# ProPrj___2025-12-14-16-21-23.net
KiCad netlist of a schematic drawn in EasyEDA Pro
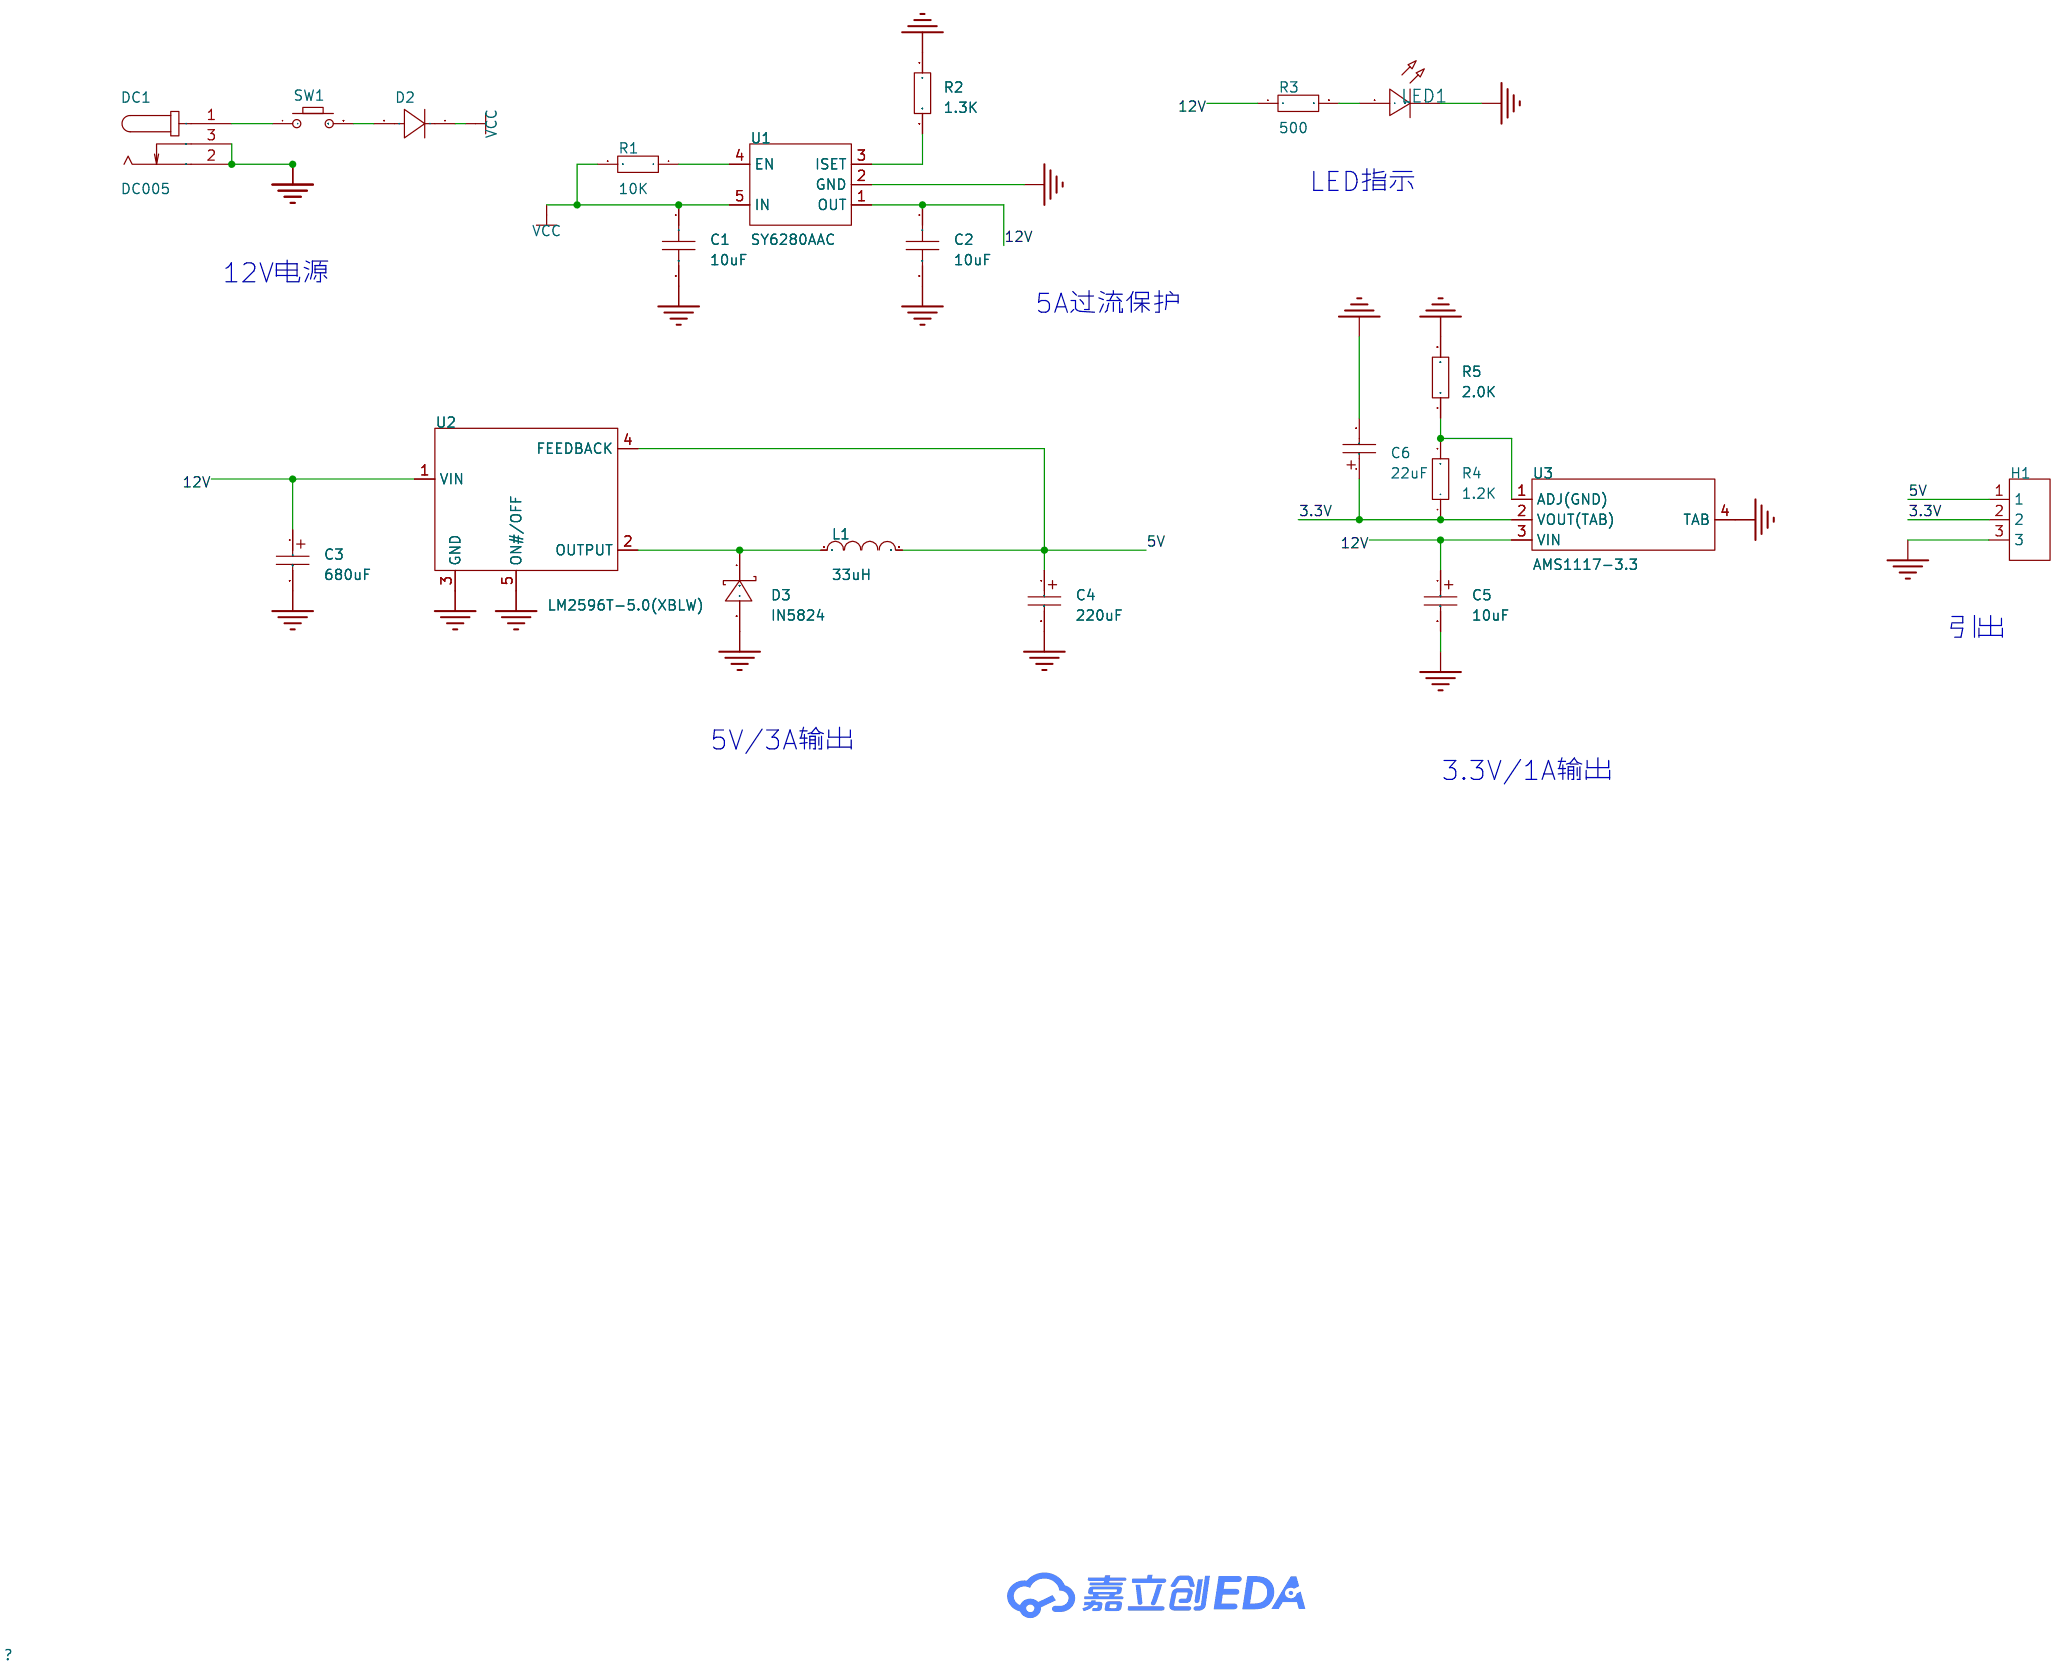
[diagram p0: schematic sheet]

(export (version "E")
  (design (tool "Eeschema 10.0.6"))
  (components
    (comp (ref "C1")
      (value "10uF")
      (footprint "easyedapro:C0603")
      (libsource (lib "easyedapro") (part "Capacitance"))
    )
    (comp (ref "C2")
      (value "10uF")
      (footprint "easyedapro:C0603")
      (libsource (lib "easyedapro") (part "Capacitance"))
    )
    (comp (ref "C3")
      (value "680uF")
      (footprint "easyedapro:C_Ele_SMD_3x5.4mm")
      (libsource (lib "easyedapro") (part "CAP"))
    )
    (comp (ref "C4")
      (value "220uF")
      (footprint "easyedapro:C_Ele_SMD_3x5.4mm")
      (libsource (lib "easyedapro") (part "CAP"))
    )
    (comp (ref "C5")
      (value "10uF")
      (footprint "easyedapro:C_Ele_SMD_3x5.4mm")
      (libsource (lib "easyedapro") (part "CAP"))
    )
    (comp (ref "C6")
      (value "22uF")
      (footprint "easyedapro:C_Ele_SMD_3x5.4mm")
      (libsource (lib "easyedapro") (part "CAP"))
    )
    (comp (ref "D2")
      (value "~")
      (footprint "easyedapro:DO_1N4007")
      (libsource (lib "easyedapro") (part "D_1N4007"))
    )
    (comp (ref "D3")
      (value "IN5824")
      (footprint "easyedapro:SMAF_L3.5-W2.6-LS4.7-RD")
      (libsource (lib "easyedapro") (part "IN5824"))
    )
    (comp (ref "DC1")
      (value "DC005")
      (footprint "easyedapro:DC-IN-TH_DC005")
      (description "连接器类型:DC电源插座;安装方式:弯插;触点内径:2mm;触点外径:6.3mm;额定电流:500mA;额定电压:12V;工作温度:-30°C~+70°C;")
      (fields (field (name "Manufacturer") "SHOU HAN(首韩)"))
      (libsource (lib "easyedapro") (part "DC005_C431533"))
    )
    (comp (ref "H1")
      (value "~")
      (footprint "easyedapro:HDR-TH_3P-P2.54-V-F")
      (libsource (lib "easyedapro") (part "PM254V-11-03-H85"))
    )
    (comp (ref "L1")
      (value "33uH")
      (footprint "easyedapro:L0603")
      (libsource (lib "easyedapro") (part "SDFL1608S100KTF"))
    )
    (comp (ref "LED1")
      (value "~")
      (footprint "easyedapro:LED_0603")
      (libsource (lib "easyedapro") (part "LED_R"))
    )
    (comp (ref "R1") (value "10K") (footprint "easyedapro:R0603") (libsource (lib "easyedapro") (part "电阻")))
    (comp (ref "R2") (value "1.3K") (footprint "easyedapro:R0603") (libsource (lib "easyedapro") (part "电阻")))
    (comp (ref "R3") (value "500") (footprint "easyedapro:R0603") (libsource (lib "easyedapro") (part "电阻")))
    (comp (ref "R4") (value "1.2K") (footprint "easyedapro:R0603") (libsource (lib "easyedapro") (part "电阻")))
    (comp (ref "R5") (value "2.0K") (footprint "easyedapro:R0603") (libsource (lib "easyedapro") (part "电阻")))
    (comp (ref "SW1")
      (value "~")
      (footprint "easyedapro:Key_TH_3.5x6x4.3")
      (libsource (lib "easyedapro") (part "Key_TH_3.5x6x4.3"))
    )
    (comp (ref "U1")
      (value "SY6280AAC")
      (footprint "easyedapro:SOT-23-5_L3.0-W1.7-P0.95-LS2.8-BR")
      (libsource (lib "easyedapro") (part "SY6280AAC_C9900003867"))
    )
    (comp (ref "U2")
      (value "LM2596T-5.0(XBLW)")
      (footprint "easyedapro:TO-220-5L_L10.2-W4.5-P1.71-L")
      (description "功能类型:降压型;工作电压:6V~40V;输出电压:5V;输出电流:3A;输出类型:固定;")
      (fields (field (name "Manufacturer") "XBLW(芯伯乐)"))
      (libsource (lib "easyedapro") (part "LM2596T-5.0(XBLW)"))
    )
    (comp (ref "U3")
      (value "AMS1117-3.3")
      (footprint "easyedapro:SOT-223-4_L6.5-W3.5-P2.30-LS7.0-BR")
      (description "输出类型:固定;工作电压:12V;输出电压:3.3V;输出电流:1A;电源纹波抑制比(PSRR):60dB@(120Hz);输出极性:正极;")
      (fields (field (name "Manufacturer") "UMW(友台半导体)"))
      (libsource (lib "easyedapro") (part "AMS1117-3.3_C347222"))
    )
  )
  (nets
    (net (code "1") (name "/3.3V") (class "Default")
      (node (ref "C6") (pin "1") (pinfunction "1_1") (pintype "input"))
      (node (ref "H1") (pin "2") (pinfunction "2_2") (pintype "unspecified"))
      (node (ref "R4") (pin "1") (pinfunction "1_1") (pintype "input"))
      (node (ref "U3") (pin "2") (pinfunction "VOUT(TAB)_2") (pintype "unspecified"))
    )
    (net (code "2") (name "/5V") (class "Default")
      (node (ref "C4") (pin "1") (pinfunction "1_1") (pintype "input"))
      (node (ref "H1") (pin "1") (pinfunction "1_1") (pintype "unspecified"))
      (node (ref "L1") (pin "2") (pinfunction "2_2") (pintype "unspecified"))
      (node (ref "U2") (pin "4") (pinfunction "FEEDBACK_4") (pintype "unspecified"))
    )
    (net (code "3") (name "/12V") (class "Default")
      (node (ref "C2") (pin "1") (pinfunction "1_1") (pintype "input"))
      (node (ref "C3") (pin "1") (pinfunction "1_1") (pintype "input"))
      (node (ref "C5") (pin "1") (pinfunction "1_1") (pintype "input"))
      (node (ref "R3") (pin "1") (pinfunction "1_1") (pintype "input"))
      (node (ref "U1") (pin "1") (pinfunction "OUT_1") (pintype "unspecified"))
      (node (ref "U2") (pin "1") (pinfunction "VIN_1") (pintype "unspecified"))
      (node (ref "U3") (pin "3") (pinfunction "VIN_3") (pintype "unspecified"))
    )
    (net (code "4") (name "GND") (class "Default")
      (node (ref "C1") (pin "2") (pinfunction "2_2") (pintype "input"))
      (node (ref "C2") (pin "2") (pinfunction "2_2") (pintype "input"))
      (node (ref "C3") (pin "2") (pinfunction "2_2") (pintype "input"))
      (node (ref "C4") (pin "2") (pinfunction "2_2") (pintype "input"))
      (node (ref "C5") (pin "2") (pinfunction "2_2") (pintype "input"))
      (node (ref "C6") (pin "2") (pinfunction "2_2") (pintype "input"))
      (node (ref "D3") (pin "2") (pinfunction "A_2") (pintype "unspecified"))
      (node (ref "DC1") (pin "2") (pinfunction "2_2") (pintype "unspecified"))
      (node (ref "DC1") (pin "3") (pinfunction "3_3") (pintype "unspecified"))
      (node (ref "H1") (pin "3") (pinfunction "3_3") (pintype "unspecified"))
      (node (ref "LED1") (pin "1") (pinfunction "C_1") (pintype "input"))
      (node (ref "R2") (pin "1") (pinfunction "1_1") (pintype "input"))
      (node (ref "R5") (pin "2") (pinfunction "2_2") (pintype "input"))
      (node (ref "U1") (pin "2") (pinfunction "GND_2") (pintype "unspecified"))
      (node (ref "U2") (pin "3") (pinfunction "GND_3") (pintype "unspecified"))
      (node (ref "U2") (pin "5") (pinfunction "ON#/OFF_5") (pintype "unspecified"))
      (node (ref "U3") (pin "4") (pinfunction "TAB_4") (pintype "unspecified"))
    )
    (net (code "5") (name "Net-(D2-A)") (class "Default")
      (node (ref "D2") (pin "2") (pinfunction "A_2") (pintype "input"))
      (node (ref "SW1") (pin "B") (pinfunction "B_B") (pintype "input"))
    )
    (net (code "6") (name "Net-(D3-C)") (class "Default")
      (node (ref "D3") (pin "1") (pinfunction "C_1") (pintype "unspecified"))
      (node (ref "L1") (pin "1") (pinfunction "1_1") (pintype "unspecified"))
      (node (ref "U2") (pin "2") (pinfunction "OUTPUT_2") (pintype "unspecified"))
    )
    (net (code "7") (name "Net-(DC1-Pad1)") (class "Default")
      (node (ref "DC1") (pin "1") (pinfunction "1_1") (pintype "unspecified"))
      (node (ref "SW1") (pin "A") (pinfunction "A_A") (pintype "input"))
    )
    (net (code "8") (name "Net-(LED1-A)") (class "Default")
      (node (ref "LED1") (pin "2") (pinfunction "A_2") (pintype "input"))
      (node (ref "R3") (pin "2") (pinfunction "2_2") (pintype "input"))
    )
    (net (code "9") (name "Net-(U1-EN)") (class "Default")
      (node (ref "R1") (pin "1") (pinfunction "1_1") (pintype "input"))
      (node (ref "U1") (pin "4") (pinfunction "EN_4") (pintype "unspecified"))
    )
    (net (code "10") (name "Net-(U1-ISET)") (class "Default")
      (node (ref "R2") (pin "2") (pinfunction "2_2") (pintype "input"))
      (node (ref "U1") (pin "3") (pinfunction "ISET_3") (pintype "unspecified"))
    )
    (net (code "11") (name "Net-(U3-ADJ(GND))") (class "Default")
      (node (ref "R4") (pin "2") (pinfunction "2_2") (pintype "input"))
      (node (ref "R5") (pin "1") (pinfunction "1_1") (pintype "input"))
      (node (ref "U3") (pin "1") (pinfunction "ADJ(GND)_1") (pintype "unspecified"))
    )
    (net (code "12") (name "VCC") (class "Default")
      (node (ref "C1") (pin "1") (pinfunction "1_1") (pintype "input"))
      (node (ref "D2") (pin "1") (pinfunction "K_1") (pintype "input"))
      (node (ref "R1") (pin "2") (pinfunction "2_2") (pintype "input"))
      (node (ref "U1") (pin "5") (pinfunction "IN_5") (pintype "unspecified"))
    )
  )
)
